# Schematics_V1.net
KiCad netlist of a schematic drawn in Altium Designer
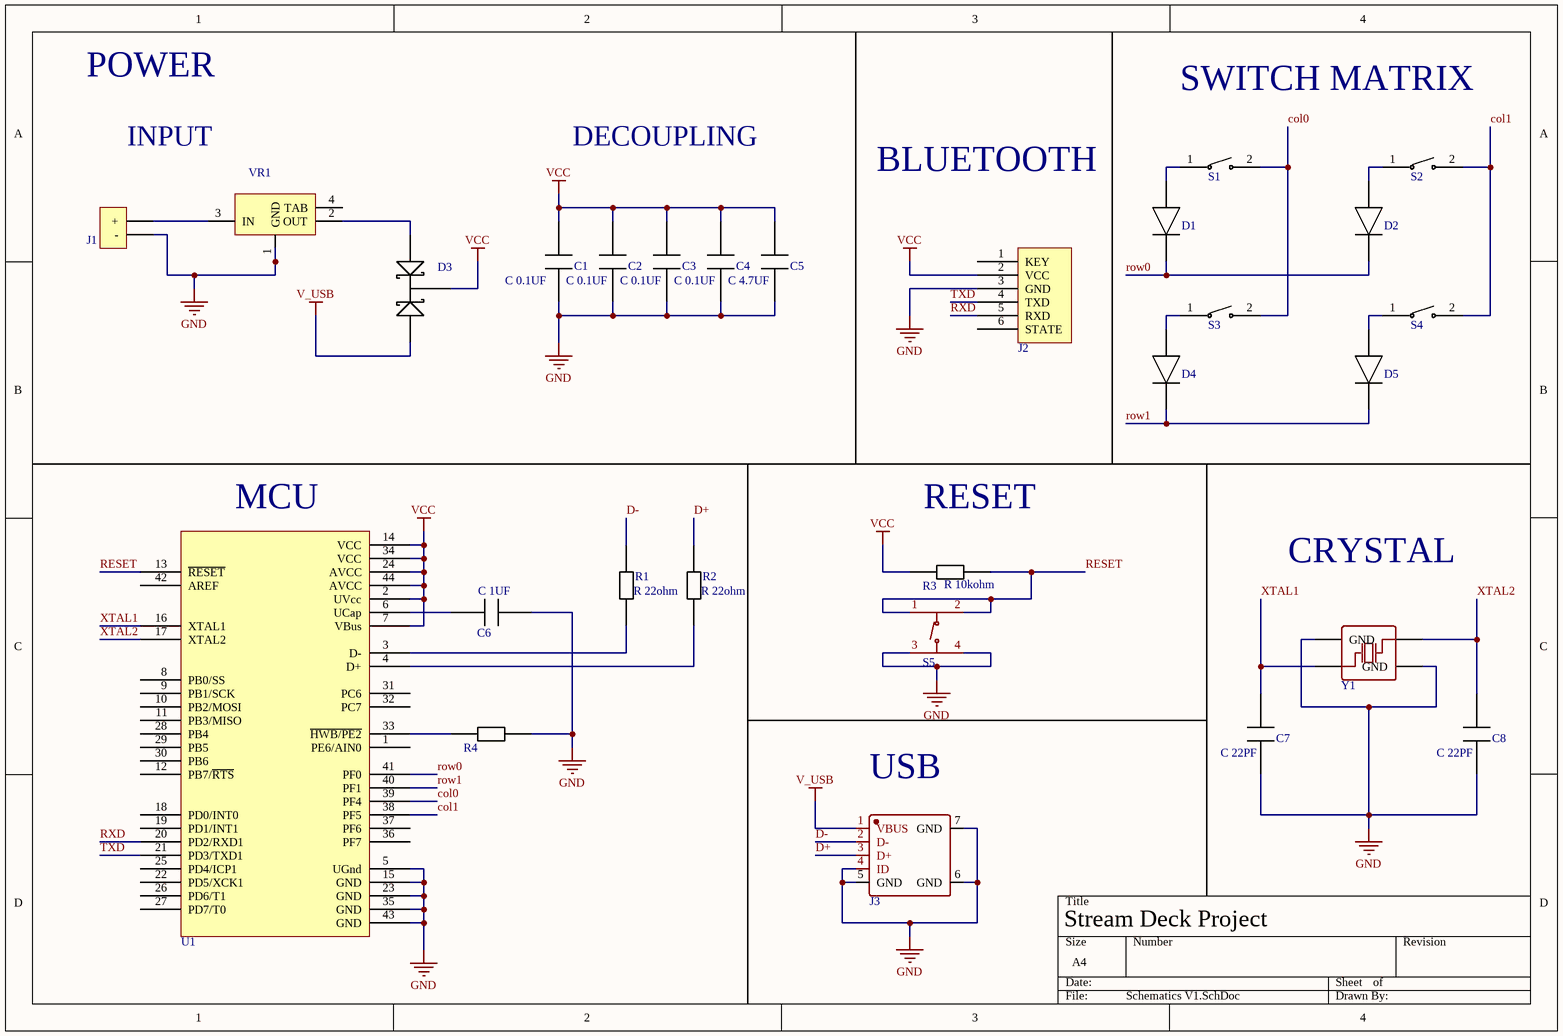
[diagram p0: Schematics V1.SchDoc]

(export (version "E")
  (design (tool "Eeschema 10.0.6"))
  (components
    (comp (ref "C1")
      (value "C 0.1UF")
      (footprint "C0805")
      (description "CAP CER 100PF 50V C0G/NP0 0805")
      (fields
        (field (name "MANUFACTURER") "Samsung")
        (field (name "MANUFACTURER PART NUMBER") "CL21C101JBANNNC")
      )
      (libsource (lib "Schlib") (part "CL21C101JBANNNC"))
    )
    (comp (ref "C2")
      (value "C 0.1UF")
      (footprint "C0805")
      (description "CAP CER 100PF 50V C0G/NP0 0805")
      (fields
        (field (name "MANUFACTURER") "Samsung")
        (field (name "MANUFACTURER PART NUMBER") "CL21C101JBANNNC")
      )
      (libsource (lib "Schlib") (part "CL21C101JBANNNC"))
    )
    (comp (ref "C3")
      (value "C 0.1UF")
      (footprint "C0805")
      (description "CAP CER 100PF 50V C0G/NP0 0805")
      (fields
        (field (name "MANUFACTURER") "Samsung")
        (field (name "MANUFACTURER PART NUMBER") "CL21C101JBANNNC")
      )
      (libsource (lib "Schlib") (part "CL21C101JBANNNC"))
    )
    (comp (ref "C4")
      (value "C 0.1UF")
      (footprint "C0805")
      (description "CAP CER 100PF 50V C0G/NP0 0805")
      (fields
        (field (name "MANUFACTURER") "Samsung")
        (field (name "MANUFACTURER PART NUMBER") "CL21C101JBANNNC")
      )
      (libsource (lib "Schlib") (part "CL21C101JBANNNC"))
    )
    (comp (ref "C5")
      (value "C 4.7UF")
      (footprint "C0805")
      (fields
        (field (name "MANUFACTURER") "Samsung")
        (field (name "MANUFACTURER PART NUMBER") "CL21A475KAQNNNE")
        (field (name "TOLERANCE") "10%")
      )
      (libsource (lib "Schlib") (part "CL21A475KAQNNNE"))
    )
    (comp (ref "C6")
      (value "C 1UF")
      (footprint "C0805")
      (fields
        (field (name "MANUFACTURER") "Samsung")
        (field (name "MANUFACTURER PART NUMBER") "CL21B105KBFNNNE")
        (field (name "TOLERANCE") "10%")
      )
      (libsource (lib "Schlib") (part "CL21B105KBFNNNE"))
    )
    (comp (ref "C7")
      (value "C 22PF")
      (footprint "C0805")
      (description "Cap Ceramic 22pF 50V C0G 5% SMD 0805 125C T/R")
      (fields
        (field (name "MANUFACTURER") "Samsung")
        (field (name "MANUFACTURER PART NUMBER") "CL21C220JBANNNC")
      )
      (libsource (lib "Schlib") (part "CL21C220JBANNNC"))
    )
    (comp (ref "C8")
      (value "C 22PF")
      (footprint "C0805")
      (description "Cap Ceramic 22pF 50V C0G 5% SMD 0805 125C T/R")
      (fields
        (field (name "MANUFACTURER") "Samsung")
        (field (name "MANUFACTURER PART NUMBER") "CL21C220JBANNNC")
      )
      (libsource (lib "Schlib") (part "CL21C220JBANNNC"))
    )
    (comp (ref "D1")
      (value "Diode")
      (footprint "Diode")
      (description "MICRO COMMERCIAL COMPONENTS - 1N4148W-TP - SWITCHING DIODE, 150mA, 100V, SOD123, FU")
      (fields (field (name "MANUFACTURER") "MCC") (field (name "MANUFACTURER PART NUMBER") "1N4148W-TP"))
      (libsource (lib "Schlib") (part "1N4148W-TP"))
    )
    (comp (ref "D2")
      (value "Diode")
      (footprint "Diode")
      (description "MICRO COMMERCIAL COMPONENTS - 1N4148W-TP - SWITCHING DIODE, 150mA, 100V, SOD123, FU")
      (fields (field (name "MANUFACTURER") "MCC") (field (name "MANUFACTURER PART NUMBER") "1N4148W-TP"))
      (libsource (lib "Schlib") (part "1N4148W-TP"))
    )
    (comp (ref "D3")
      (value "Schottky")
      (footprint "SOT-23-3_L2.9-W1.6-P1.90-LS2.8-BR")
      (description "Diode Schottky 30V 0.2A 3-Pin SOT-23 T/R")
      (fields
        (field (name "MANUFACTURER") "ON Semiconductor")
        (field (name "MANUFACTURER PART NUMBER") "BAT54CLT1G")
      )
      (libsource (lib "Schlib") (part "BAT54CLT1G"))
    )
    (comp (ref "D4")
      (value "Diode")
      (footprint "Diode")
      (description "MICRO COMMERCIAL COMPONENTS - 1N4148W-TP - SWITCHING DIODE, 150mA, 100V, SOD123, FU")
      (fields (field (name "MANUFACTURER") "MCC") (field (name "MANUFACTURER PART NUMBER") "1N4148W-TP"))
      (libsource (lib "Schlib") (part "1N4148W-TP"))
    )
    (comp (ref "D5")
      (value "Diode")
      (footprint "Diode")
      (description "MICRO COMMERCIAL COMPONENTS - 1N4148W-TP - SWITCHING DIODE, 150mA, 100V, SOD123, FU")
      (fields (field (name "MANUFACTURER") "MCC") (field (name "MANUFACTURER PART NUMBER") "1N4148W-TP"))
      (libsource (lib "Schlib") (part "1N4148W-TP"))
    )
    (comp (ref "J1")
      (value "BAT")
      (footprint "HDR-TH_2P-P2.54-V-M-1")
      (description "CONN HEADER VERT 2POS 2.54MM")
      (fields (field (name "MANUFACTURER") "Molex") (field (name "MANUFACTURER PART NUMBER") "22-28-4020"))
      (libsource (lib "Schlib") (part "22-28-4020"))
    )
    (comp (ref "J2")
      (value "HDR-Bluetooth")
      (footprint "HDR-TH_6P-P2.54-H-W8.6_A2541HWR-6P")
      (fields
        (field (name "MANUFACTURER") "CJT Connectors")
        (field (name "MANUFACTURER PART NUMBER") "A2541HWR-6P")
      )
      (libsource (lib "Schlib") (part "A2541HWR-6P"))
    )
    (comp (ref "J3")
      (value "USB")
      (footprint "USB-MINI-SMD_UX60SC-MB-5S8-80")
      (description "CONN RCPT MINI USB2.0 5POS")
      (fields
        (field (name "MANUFACTURER") "Hirose")
        (field (name "MANUFACTURER PART NUMBER") "UX60SC-MB-5S8(80)")
      )
      (libsource (lib "Schlib") (part "UX60SC-MB-5S8(80)"))
    )
    (comp (ref "R1")
      (value "R 22ohm")
      (footprint "R0805")
      (description "±1% ±200ppm/℃ 22Ω 0.125W 0805 Chip Resistor - Surface Mount ROHS")
      (fields
        (field (name "MANUFACTURER") "Uniroyal")
        (field (name "MANUFACTURER PART NUMBER") "0805W8F220JT5E")
      )
      (libsource (lib "Schlib") (part "0805W8F220JT5E"))
    )
    (comp (ref "R2")
      (value "R 22ohm")
      (footprint "R0805")
      (description "±1% ±200ppm/℃ 22Ω 0.125W 0805 Chip Resistor - Surface Mount ROHS")
      (fields
        (field (name "MANUFACTURER") "Uniroyal")
        (field (name "MANUFACTURER PART NUMBER") "0805W8F220JT5E")
      )
      (libsource (lib "Schlib") (part "0805W8F220JT5E"))
    )
    (comp (ref "R3")
      (value "R 10kohm")
      (footprint "R0805")
      (description "±1% ±100ppm/℃ 10kΩ 0.125W 0805 Chip Resistor - Surface Mount ROHS")
      (fields
        (field (name "MANUFACTURER") "Uniroyal")
        (field (name "MANUFACTURER PART NUMBER") "0805W8F1002T5E")
      )
      (libsource (lib "Schlib") (part "0805W8F1002T5E"))
    )
    (comp (ref "R4")
      (value "R 10kohm")
      (footprint "R0805")
      (description "±1% ±100ppm/℃ 10kΩ 0.125W 0805 Chip Resistor - Surface Mount ROHS")
      (fields
        (field (name "MANUFACTURER") "Uniroyal")
        (field (name "MANUFACTURER PART NUMBER") "0805W8F1002T5E")
      )
      (libsource (lib "Schlib") (part "0805W8F1002T5E"))
    )
    (comp (ref "S1") (value "Switch") (footprint "Mx_Alps_100") (libsource (lib "Schlib") (part "Switch")))
    (comp (ref "S2") (value "Switch") (footprint "Mx_Alps_100") (libsource (lib "Schlib") (part "Switch")))
    (comp (ref "S3") (value "Switch") (footprint "Mx_Alps_100") (libsource (lib "Schlib") (part "Switch")))
    (comp (ref "S4") (value "Switch") (footprint "Mx_Alps_100") (libsource (lib "Schlib") (part "Switch")))
    (comp (ref "S5")
      (value "Button")
      (footprint "SW-SMD_4P-L5.1-W5.1-P3.70-LS6.5-TL-2")
      (fields
        (field (name "MANUFACTURER") "XKB Connectivity")
        (field (name "MANUFACTURER PART NUMBER") "TS-1187A-B-A-B")
      )
      (libsource (lib "Schlib") (part "TS-1187A-B-A-B"))
    )
    (comp (ref "U1")
      (value "MCU")
      (footprint "ATMEGA32U4")
      (description "MCU 8-bit ATmega AVR RISC 32KB Flash 3.3V/5V 44-Pin TQFP")
      (fields
        (field (name "MANUFACTURER") "Microchip / Atmel")
        (field (name "MANUFACTURER PART NUMBER") "ATMEGA32U4-AU")
      )
      (libsource (lib "Schlib") (part "ATMEGA32U4-AU"))
    )
    (comp (ref "VR1")
      (value "Regulator")
      (footprint "SOT-223_L6.5-W3.5-P2.30-LS7.0-BR")
      (fields
        (field (name "MANUFACTURER") "Advanced Monolithic Systems")
        (field (name "MANUFACTURER PART NUMBER") "AMS1117-5.0")
      )
      (libsource (lib "Schlib") (part "AMS1117-5.0"))
    )
    (comp (ref "Y1")
      (value "Crystal")
      (footprint "CRYSTAL-SMD_4P-L3.2-W2.5-BL")
      (fields (field (name "MANUFACTURER") "Seiko") (field (name "MANUFACTURER PART NUMBER") "X1E0000210264"))
      (libsource (lib "Schlib") (part "X1E0000210264"))
    )
  )
  (nets
    (net (code "1") (name "/D+") (class "Default")
      (node (ref "J3") (pin "3") (pinfunction "D+_3") (pintype "passive"))
      (node (ref "R2") (pin "2") (pinfunction "2_2") (pintype "passive"))
    )
    (net (code "2") (name "/D-") (class "Default")
      (node (ref "J3") (pin "2") (pinfunction "D-_2") (pintype "passive"))
      (node (ref "R1") (pin "2") (pinfunction "2_2") (pintype "passive"))
    )
    (net (code "3") (name "/RESET") (class "Default")
      (node (ref "R3") (pin "2") (pinfunction "2_2") (pintype "passive"))
      (node (ref "S5") (pin "1") (pinfunction "A_1") (pintype "passive"))
      (node (ref "S5") (pin "2") (pinfunction "B_2") (pintype "passive"))
      (node (ref "U1") (pin "13") (pinfunction "~{RESET}_13") (pintype "passive"))
    )
    (net (code "4") (name "/RXD") (class "Default")
      (node (ref "J2") (pin "5") (pinfunction "RXD_5") (pintype "passive"))
      (node (ref "U1") (pin "20") (pinfunction "PD2/RXD1_20") (pintype "passive"))
    )
    (net (code "5") (name "/TXD") (class "Default")
      (node (ref "J2") (pin "4") (pinfunction "TXD_4") (pintype "passive"))
      (node (ref "U1") (pin "21") (pinfunction "PD3/TXD1_21") (pintype "passive"))
    )
    (net (code "6") (name "/XTAL1") (class "Default")
      (node (ref "C7") (pin "2") (pinfunction "2_2") (pintype "passive"))
      (node (ref "U1") (pin "16") (pinfunction "XTAL1_16") (pintype "passive"))
      (node (ref "Y1") (pin "1") (pinfunction "OSC1_1") (pintype "passive"))
    )
    (net (code "7") (name "/XTAL2") (class "Default")
      (node (ref "C8") (pin "2") (pinfunction "2_2") (pintype "passive"))
      (node (ref "U1") (pin "17") (pinfunction "XTAL2_17") (pintype "passive"))
      (node (ref "Y1") (pin "3") (pinfunction "OSC2_3") (pintype "passive"))
    )
    (net (code "8") (name "/col0") (class "Default")
      (node (ref "S1") (pin "2") (pinfunction "2_2") (pintype "passive"))
      (node (ref "S3") (pin "2") (pinfunction "2_2") (pintype "passive"))
      (node (ref "U1") (pin "39") (pinfunction "PF4_39") (pintype "passive"))
    )
    (net (code "9") (name "/col1") (class "Default")
      (node (ref "S2") (pin "2") (pinfunction "2_2") (pintype "passive"))
      (node (ref "S4") (pin "2") (pinfunction "2_2") (pintype "passive"))
      (node (ref "U1") (pin "38") (pinfunction "PF5_38") (pintype "passive"))
    )
    (net (code "10") (name "/row0") (class "Default")
      (node (ref "D1") (pin "1") (pinfunction "1_1") (pintype "passive"))
      (node (ref "D2") (pin "1") (pinfunction "1_1") (pintype "passive"))
      (node (ref "U1") (pin "41") (pinfunction "PF0_41") (pintype "passive"))
    )
    (net (code "11") (name "/row1") (class "Default")
      (node (ref "D4") (pin "1") (pinfunction "1_1") (pintype "passive"))
      (node (ref "D5") (pin "1") (pinfunction "1_1") (pintype "passive"))
      (node (ref "U1") (pin "40") (pinfunction "PF1_40") (pintype "passive"))
    )
    (net (code "12") (name "GND") (class "Default")
      (node (ref "C1") (pin "1") (pinfunction "1_1") (pintype "passive"))
      (node (ref "C2") (pin "1") (pinfunction "1_1") (pintype "passive"))
      (node (ref "C3") (pin "1") (pinfunction "1_1") (pintype "passive"))
      (node (ref "C4") (pin "1") (pinfunction "1_1") (pintype "passive"))
      (node (ref "C5") (pin "1") (pinfunction "1_1") (pintype "passive"))
      (node (ref "C6") (pin "2") (pinfunction "2_2") (pintype "passive"))
      (node (ref "C7") (pin "1") (pinfunction "1_1") (pintype "passive"))
      (node (ref "C8") (pin "1") (pinfunction "1_1") (pintype "passive"))
      (node (ref "J1") (pin "2") (pinfunction "-_2") (pintype "passive"))
      (node (ref "J2") (pin "3") (pinfunction "GND_3") (pintype "passive"))
      (node (ref "J3") (pin "4") (pinfunction "ID_4") (pintype "passive"))
      (node (ref "J3") (pin "5") (pinfunction "GND_5") (pintype "passive"))
      (node (ref "J3") (pin "6") (pinfunction "GND_6") (pintype "passive"))
      (node (ref "J3") (pin "7") (pinfunction "GND_7") (pintype "passive"))
      (node (ref "R4") (pin "2") (pinfunction "2_2") (pintype "passive"))
      (node (ref "S5") (pin "3") (pinfunction "C_3") (pintype "passive"))
      (node (ref "S5") (pin "4") (pinfunction "D_4") (pintype "passive"))
      (node (ref "U1") (pin "15") (pinfunction "GND_15") (pintype "passive"))
      (node (ref "U1") (pin "23") (pinfunction "GND_23") (pintype "passive"))
      (node (ref "U1") (pin "35") (pinfunction "GND_35") (pintype "passive"))
      (node (ref "U1") (pin "43") (pinfunction "GND_43") (pintype "passive"))
      (node (ref "U1") (pin "5") (pinfunction "UGnd_5") (pintype "passive"))
      (node (ref "VR1") (pin "1") (pinfunction "GND_1") (pintype "passive"))
      (node (ref "Y1") (pin "2") (pinfunction "GND_2") (pintype "passive"))
      (node (ref "Y1") (pin "4") (pinfunction "GND_4") (pintype "passive"))
    )
    (net (code "13") (name "Net-(D1-Pad2)") (class "Default")
      (node (ref "D1") (pin "2") (pinfunction "2_2") (pintype "passive"))
      (node (ref "S1") (pin "1") (pinfunction "1_1") (pintype "passive"))
    )
    (net (code "14") (name "Net-(D2-Pad2)") (class "Default")
      (node (ref "D2") (pin "2") (pinfunction "2_2") (pintype "passive"))
      (node (ref "S2") (pin "1") (pinfunction "1_1") (pintype "passive"))
    )
    (net (code "15") (name "Net-(D4-Pad2)") (class "Default")
      (node (ref "D4") (pin "2") (pinfunction "2_2") (pintype "passive"))
      (node (ref "S3") (pin "1") (pinfunction "1_1") (pintype "passive"))
    )
    (net (code "16") (name "Net-(D5-Pad2)") (class "Default")
      (node (ref "D5") (pin "2") (pinfunction "2_2") (pintype "passive"))
      (node (ref "S4") (pin "1") (pinfunction "1_1") (pintype "passive"))
    )
    (net (code "17") (name "Net-(J1-+)") (class "Default")
      (node (ref "J1") (pin "1") (pinfunction "+_1") (pintype "passive"))
      (node (ref "VR1") (pin "3") (pinfunction "IN_3") (pintype "passive"))
    )
    (net (code "18") (name "Net-(U1-D+)") (class "Default")
      (node (ref "R2") (pin "1") (pinfunction "1_1") (pintype "passive"))
      (node (ref "U1") (pin "4") (pinfunction "D+_4") (pintype "passive"))
    )
    (net (code "19") (name "Net-(U1-D-)") (class "Default")
      (node (ref "R1") (pin "1") (pinfunction "1_1") (pintype "passive"))
      (node (ref "U1") (pin "3") (pinfunction "D-_3") (pintype "passive"))
    )
    (net (code "20") (name "Net-(U1-UCap)") (class "Default")
      (node (ref "C6") (pin "1") (pinfunction "1_1") (pintype "passive"))
      (node (ref "U1") (pin "6") (pinfunction "UCap_6") (pintype "passive"))
    )
    (net (code "21") (name "Net-(U1-~{HWB{slash}PE2})") (class "Default")
      (node (ref "R4") (pin "1") (pinfunction "1_1") (pintype "passive"))
      (node (ref "U1") (pin "33") (pinfunction "~{HWB/PE2}_33") (pintype "passive"))
    )
    (net (code "22") (name "Net-(VR1-OUT)") (class "Default")
      (node (ref "D3") (pin "2") (pinfunction "2_2") (pintype "passive"))
      (node (ref "VR1") (pin "2") (pinfunction "OUT_2") (pintype "passive"))
    )
    (net (code "23") (name "VCC") (class "Default")
      (node (ref "C1") (pin "2") (pinfunction "2_2") (pintype "passive"))
      (node (ref "C2") (pin "2") (pinfunction "2_2") (pintype "passive"))
      (node (ref "C3") (pin "2") (pinfunction "2_2") (pintype "passive"))
      (node (ref "C4") (pin "2") (pinfunction "2_2") (pintype "passive"))
      (node (ref "C5") (pin "2") (pinfunction "2_2") (pintype "passive"))
      (node (ref "D3") (pin "3") (pinfunction "3_3") (pintype "passive"))
      (node (ref "J2") (pin "2") (pinfunction "VCC_2") (pintype "passive"))
      (node (ref "R3") (pin "1") (pinfunction "1_1") (pintype "passive"))
      (node (ref "U1") (pin "14") (pinfunction "VCC_14") (pintype "passive"))
      (node (ref "U1") (pin "2") (pinfunction "UVcc_2") (pintype "passive"))
      (node (ref "U1") (pin "24") (pinfunction "AVCC_24") (pintype "passive"))
      (node (ref "U1") (pin "34") (pinfunction "VCC_34") (pintype "passive"))
      (node (ref "U1") (pin "44") (pinfunction "AVCC_44") (pintype "passive"))
      (node (ref "U1") (pin "7") (pinfunction "VBus_7") (pintype "passive"))
    )
    (net (code "24") (name "V_USB") (class "Default")
      (node (ref "D3") (pin "1") (pinfunction "1_1") (pintype "passive"))
      (node (ref "J3") (pin "1") (pinfunction "VBUS_1") (pintype "passive"))
    )
    (net (code "25") (name "unconnected-(J2-KEY-Pad1)") (class "Default")
      (node (ref "J2") (pin "1") (pinfunction "KEY_1") (pintype "passive"))
    )
    (net (code "26") (name "unconnected-(J2-STATE-Pad6)") (class "Default")
      (node (ref "J2") (pin "6") (pinfunction "STATE_6") (pintype "passive"))
    )
    (net (code "27") (name "unconnected-(U1-AREF-Pad42)") (class "Default")
      (node (ref "U1") (pin "42") (pinfunction "AREF_42") (pintype "passive"))
    )
    (net (code "28") (name "unconnected-(U1-PB0{slash}SS-Pad8)") (class "Default")
      (node (ref "U1") (pin "8") (pinfunction "PB0/SS_8") (pintype "passive"))
    )
    (net (code "29") (name "unconnected-(U1-PB1{slash}SCK-Pad9)") (class "Default")
      (node (ref "U1") (pin "9") (pinfunction "PB1/SCK_9") (pintype "passive"))
    )
    (net (code "30") (name "unconnected-(U1-PB2{slash}MOSI-Pad10)") (class "Default")
      (node (ref "U1") (pin "10") (pinfunction "PB2/MOSI_10") (pintype "passive"))
    )
    (net (code "31") (name "unconnected-(U1-PB3{slash}MISO-Pad11)") (class "Default")
      (node (ref "U1") (pin "11") (pinfunction "PB3/MISO_11") (pintype "passive"))
    )
    (net (code "32") (name "unconnected-(U1-PB4-Pad28)") (class "Default")
      (node (ref "U1") (pin "28") (pinfunction "PB4_28") (pintype "passive"))
    )
    (net (code "33") (name "unconnected-(U1-PB5-Pad29)") (class "Default")
      (node (ref "U1") (pin "29") (pinfunction "PB5_29") (pintype "passive"))
    )
    (net (code "34") (name "unconnected-(U1-PB6-Pad30)") (class "Default")
      (node (ref "U1") (pin "30") (pinfunction "PB6_30") (pintype "passive"))
    )
    (net (code "35") (name "unconnected-(U1-PB7{slash}~{RTS}-Pad12)") (class "Default")
      (node (ref "U1") (pin "12") (pinfunction "PB7/~{RTS}_12") (pintype "passive"))
    )
    (net (code "36") (name "unconnected-(U1-PC6-Pad31)") (class "Default")
      (node (ref "U1") (pin "31") (pinfunction "PC6_31") (pintype "passive"))
    )
    (net (code "37") (name "unconnected-(U1-PC7-Pad32)") (class "Default")
      (node (ref "U1") (pin "32") (pinfunction "PC7_32") (pintype "passive"))
    )
    (net (code "38") (name "unconnected-(U1-PD0{slash}INT0-Pad18)") (class "Default")
      (node (ref "U1") (pin "18") (pinfunction "PD0/INT0_18") (pintype "passive"))
    )
    (net (code "39") (name "unconnected-(U1-PD1{slash}INT1-Pad19)") (class "Default")
      (node (ref "U1") (pin "19") (pinfunction "PD1/INT1_19") (pintype "passive"))
    )
    (net (code "40") (name "unconnected-(U1-PD4{slash}ICP1-Pad25)") (class "Default")
      (node (ref "U1") (pin "25") (pinfunction "PD4/ICP1_25") (pintype "passive"))
    )
    (net (code "41") (name "unconnected-(U1-PD5{slash}XCK1-Pad22)") (class "Default")
      (node (ref "U1") (pin "22") (pinfunction "PD5/XCK1_22") (pintype "passive"))
    )
    (net (code "42") (name "unconnected-(U1-PD6{slash}T1-Pad26)") (class "Default")
      (node (ref "U1") (pin "26") (pinfunction "PD6/T1_26") (pintype "passive"))
    )
    (net (code "43") (name "unconnected-(U1-PD7{slash}T0-Pad27)") (class "Default")
      (node (ref "U1") (pin "27") (pinfunction "PD7/T0_27") (pintype "passive"))
    )
    (net (code "44") (name "unconnected-(U1-PE6{slash}AIN0-Pad1)") (class "Default")
      (node (ref "U1") (pin "1") (pinfunction "PE6/AIN0_1") (pintype "passive"))
    )
    (net (code "45") (name "unconnected-(U1-PF6-Pad37)") (class "Default")
      (node (ref "U1") (pin "37") (pinfunction "PF6_37") (pintype "passive"))
    )
    (net (code "46") (name "unconnected-(U1-PF7-Pad36)") (class "Default")
      (node (ref "U1") (pin "36") (pinfunction "PF7_36") (pintype "passive"))
    )
    (net (code "47") (name "unconnected-(VR1-TAB-Pad4)") (class "Default")
      (node (ref "VR1") (pin "4") (pinfunction "TAB_4") (pintype "passive"))
    )
  )
)
